# umodular_midi4_rev01.net
KiCad netlist of a schematic drawn in EAGLE
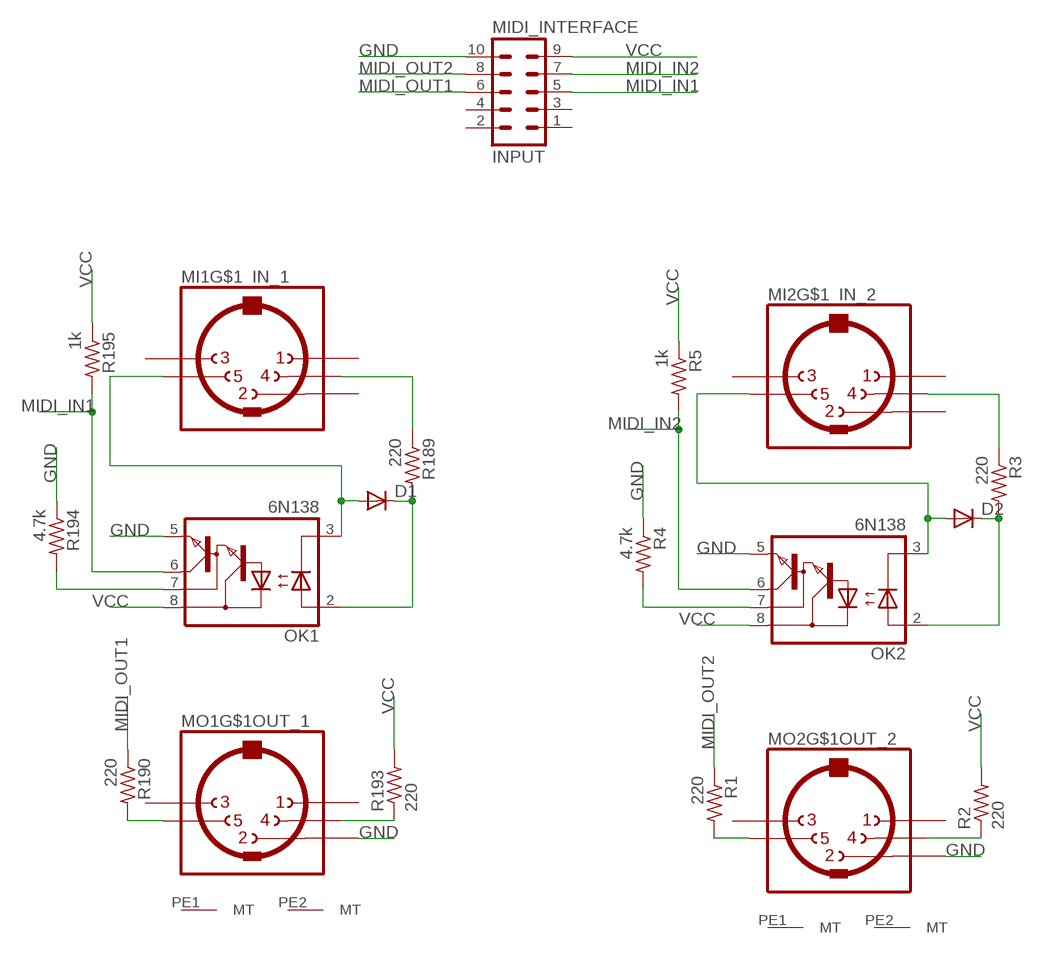
[diagram p0: schematic, sheet 1]

(export (version "E")
  (design (tool "Eeschema 10.0.6"))
  (components
    (comp (ref "D1")
      (value "1N4148DO35-7")
      (footprint "eagle-import:DO35-7")
      (libsource (lib "eagle-import") (part "1N4148DO35-7"))
    )
    (comp (ref "D2")
      (value "1N4148DO35-7")
      (footprint "eagle-import:DO35-7")
      (libsource (lib "eagle-import") (part "1N4148DO35-7"))
    )
    (comp (ref "MI1")
      (value "IN_1")
      (footprint "eagle-import:CP-2350")
      (libsource (lib "eagle-import") (part "MIDIJACK"))
    )
    (comp (ref "MI2")
      (value "IN_2")
      (footprint "eagle-import:CP-2350")
      (libsource (lib "eagle-import") (part "MIDIJACK"))
    )
    (comp (ref "MIDI_INTERFACE")
      (value "INPUT")
      (footprint "eagle-import:MA05-2")
      (libsource (lib "eagle-import") (part "MA05-2"))
    )
    (comp (ref "MO1")
      (value "OUT_1")
      (footprint "eagle-import:CP-2350")
      (libsource (lib "eagle-import") (part "MIDIJACK"))
    )
    (comp (ref "MO2")
      (value "OUT_2")
      (footprint "eagle-import:CP-2350")
      (libsource (lib "eagle-import") (part "MIDIJACK"))
    )
    (comp (ref "OK1")
      (value "6N138")
      (footprint "eagle-import:DIL08")
      (fields (field (name "MF") "VISHAY/TELEFUNKEN"))
      (libsource (lib "eagle-import") (part "6N138"))
    )
    (comp (ref "OK2")
      (value "6N138")
      (footprint "eagle-import:DIL08")
      (fields (field (name "MF") "VISHAY/TELEFUNKEN"))
      (libsource (lib "eagle-import") (part "6N138"))
    )
    (comp (ref "R1")
      (value "220")
      (footprint "eagle-import:0204_7@1")
      (libsource (lib "eagle-import") (part "R-US_0204/7"))
    )
    (comp (ref "R2")
      (value "220")
      (footprint "eagle-import:0204_7@1")
      (libsource (lib "eagle-import") (part "R-US_0204/7"))
    )
    (comp (ref "R3")
      (value "220")
      (footprint "eagle-import:0204_7@1")
      (libsource (lib "eagle-import") (part "R-US_0204/7"))
    )
    (comp (ref "R4")
      (value "4.7k")
      (footprint "eagle-import:0204_7@1")
      (libsource (lib "eagle-import") (part "R-US_0204/7"))
    )
    (comp (ref "R5")
      (value "1k")
      (footprint "eagle-import:0204_7@1")
      (libsource (lib "eagle-import") (part "R-US_0204/7"))
    )
    (comp (ref "R189")
      (value "220")
      (footprint "eagle-import:0204_7@1")
      (libsource (lib "eagle-import") (part "R-US_0204/7"))
    )
    (comp (ref "R190")
      (value "220")
      (footprint "eagle-import:0204_7@1")
      (libsource (lib "eagle-import") (part "R-US_0204/7"))
    )
    (comp (ref "R193")
      (value "220")
      (footprint "eagle-import:0204_7@1")
      (libsource (lib "eagle-import") (part "R-US_0204/7"))
    )
    (comp (ref "R194")
      (value "4.7k")
      (footprint "eagle-import:0204_7@1")
      (libsource (lib "eagle-import") (part "R-US_0204/7"))
    )
    (comp (ref "R195")
      (value "1k")
      (footprint "eagle-import:0204_7@1")
      (libsource (lib "eagle-import") (part "R-US_0204/7"))
    )
  )
  (nets
    (net (code "1") (name "/GND") (class "Default")
      (node (ref "MIDI_INTERFACE") (pin "10") (pinfunction "10_10") (pintype "passive"))
      (node (ref "MO1") (pin "2") (pinfunction "2_2") (pintype "passive"))
      (node (ref "MO2") (pin "2") (pinfunction "2_2") (pintype "passive"))
      (node (ref "OK1") (pin "5") (pinfunction "GND_5") (pintype "passive"))
      (node (ref "OK2") (pin "5") (pinfunction "GND_5") (pintype "passive"))
      (node (ref "R194") (pin "1") (pinfunction "1_1") (pintype "passive"))
      (node (ref "R4") (pin "1") (pinfunction "1_1") (pintype "passive"))
    )
    (net (code "2") (name "/MIDI_IN1") (class "Default")
      (node (ref "MIDI_INTERFACE") (pin "5") (pinfunction "5_5") (pintype "passive"))
      (node (ref "OK1") (pin "6") (pinfunction "VO_6") (pintype "passive"))
      (node (ref "R195") (pin "2") (pinfunction "2_2") (pintype "passive"))
    )
    (net (code "3") (name "/MIDI_IN2") (class "Default")
      (node (ref "MIDI_INTERFACE") (pin "7") (pinfunction "7_7") (pintype "passive"))
      (node (ref "OK2") (pin "6") (pinfunction "VO_6") (pintype "passive"))
      (node (ref "R5") (pin "2") (pinfunction "2_2") (pintype "passive"))
    )
    (net (code "4") (name "/MIDI_OUT1") (class "Default")
      (node (ref "MIDI_INTERFACE") (pin "6") (pinfunction "6_6") (pintype "passive"))
      (node (ref "R190") (pin "1") (pinfunction "1_1") (pintype "passive"))
    )
    (net (code "5") (name "/MIDI_OUT2") (class "Default")
      (node (ref "MIDI_INTERFACE") (pin "8") (pinfunction "8_8") (pintype "passive"))
      (node (ref "R1") (pin "1") (pinfunction "1_1") (pintype "passive"))
    )
    (net (code "6") (name "/VCC") (class "Default")
      (node (ref "MIDI_INTERFACE") (pin "9") (pinfunction "9_9") (pintype "passive"))
      (node (ref "OK1") (pin "8") (pinfunction "VCC_8") (pintype "passive"))
      (node (ref "OK2") (pin "8") (pinfunction "VCC_8") (pintype "passive"))
      (node (ref "R193") (pin "2") (pinfunction "2_2") (pintype "passive"))
      (node (ref "R195") (pin "1") (pinfunction "1_1") (pintype "passive"))
      (node (ref "R2") (pin "2") (pinfunction "2_2") (pintype "passive"))
      (node (ref "R5") (pin "1") (pinfunction "1_1") (pintype "passive"))
    )
    (net (code "7") (name "Net-(MI1-Pad4)") (class "Default")
      (node (ref "MI1") (pin "4") (pinfunction "4_4") (pintype "passive"))
      (node (ref "R189") (pin "1") (pinfunction "1_1") (pintype "passive"))
    )
    (net (code "8") (name "Net-(MI2-Pad4)") (class "Default")
      (node (ref "MI2") (pin "4") (pinfunction "4_4") (pintype "passive"))
      (node (ref "R3") (pin "1") (pinfunction "1_1") (pintype "passive"))
    )
    (net (code "9") (name "Net-(MO1-Pad4)") (class "Default")
      (node (ref "MO1") (pin "4") (pinfunction "4_4") (pintype "passive"))
      (node (ref "R193") (pin "1") (pinfunction "1_1") (pintype "passive"))
    )
    (net (code "10") (name "Net-(MO1-Pad5)") (class "Default")
      (node (ref "MO1") (pin "5") (pinfunction "5_5") (pintype "passive"))
      (node (ref "R190") (pin "2") (pinfunction "2_2") (pintype "passive"))
    )
    (net (code "11") (name "Net-(MO2-Pad4)") (class "Default")
      (node (ref "MO2") (pin "4") (pinfunction "4_4") (pintype "passive"))
      (node (ref "R2") (pin "1") (pinfunction "1_1") (pintype "passive"))
    )
    (net (code "12") (name "Net-(MO2-Pad5)") (class "Default")
      (node (ref "MO2") (pin "5") (pinfunction "5_5") (pintype "passive"))
      (node (ref "R1") (pin "2") (pinfunction "2_2") (pintype "passive"))
    )
    (net (code "13") (name "Net-(OK1-A)") (class "Default")
      (node (ref "D1") (pin "C") (pinfunction "C_C") (pintype "passive"))
      (node (ref "OK1") (pin "2") (pinfunction "A_2") (pintype "passive"))
      (node (ref "R189") (pin "2") (pinfunction "2_2") (pintype "passive"))
    )
    (net (code "14") (name "Net-(OK1-C)") (class "Default")
      (node (ref "D1") (pin "A") (pinfunction "A_A") (pintype "passive"))
      (node (ref "MI1") (pin "5") (pinfunction "5_5") (pintype "passive"))
      (node (ref "OK1") (pin "3") (pinfunction "C_3") (pintype "passive"))
    )
    (net (code "15") (name "Net-(OK1-VB)") (class "Default")
      (node (ref "OK1") (pin "7") (pinfunction "VB_7") (pintype "passive"))
      (node (ref "R194") (pin "2") (pinfunction "2_2") (pintype "passive"))
    )
    (net (code "16") (name "Net-(OK2-A)") (class "Default")
      (node (ref "D2") (pin "C") (pinfunction "C_C") (pintype "passive"))
      (node (ref "OK2") (pin "2") (pinfunction "A_2") (pintype "passive"))
      (node (ref "R3") (pin "2") (pinfunction "2_2") (pintype "passive"))
    )
    (net (code "17") (name "Net-(OK2-C)") (class "Default")
      (node (ref "D2") (pin "A") (pinfunction "A_A") (pintype "passive"))
      (node (ref "MI2") (pin "5") (pinfunction "5_5") (pintype "passive"))
      (node (ref "OK2") (pin "3") (pinfunction "C_3") (pintype "passive"))
    )
    (net (code "18") (name "Net-(OK2-VB)") (class "Default")
      (node (ref "OK2") (pin "7") (pinfunction "VB_7") (pintype "passive"))
      (node (ref "R4") (pin "2") (pinfunction "2_2") (pintype "passive"))
    )
    (net (code "19") (name "unconnected-(MI1-Pad1)") (class "Default")
      (node (ref "MI1") (pin "1") (pinfunction "1_1") (pintype "passive"))
    )
    (net (code "20") (name "unconnected-(MI1-Pad2)") (class "Default")
      (node (ref "MI1") (pin "2") (pinfunction "2_2") (pintype "passive"))
    )
    (net (code "21") (name "unconnected-(MI1-Pad3)") (class "Default")
      (node (ref "MI1") (pin "3") (pinfunction "3_3") (pintype "passive"))
    )
    (net (code "22") (name "unconnected-(MI2-Pad1)") (class "Default")
      (node (ref "MI2") (pin "1") (pinfunction "1_1") (pintype "passive"))
    )
    (net (code "23") (name "unconnected-(MI2-Pad2)") (class "Default")
      (node (ref "MI2") (pin "2") (pinfunction "2_2") (pintype "passive"))
    )
    (net (code "24") (name "unconnected-(MI2-Pad3)") (class "Default")
      (node (ref "MI2") (pin "3") (pinfunction "3_3") (pintype "passive"))
    )
    (net (code "25") (name "unconnected-(MIDI_INTERFACE-Pad1)") (class "Default")
      (node (ref "MIDI_INTERFACE") (pin "1") (pinfunction "1_1") (pintype "passive"))
    )
    (net (code "26") (name "unconnected-(MIDI_INTERFACE-Pad2)") (class "Default")
      (node (ref "MIDI_INTERFACE") (pin "2") (pinfunction "2_2") (pintype "passive"))
    )
    (net (code "27") (name "unconnected-(MIDI_INTERFACE-Pad3)") (class "Default")
      (node (ref "MIDI_INTERFACE") (pin "3") (pinfunction "3_3") (pintype "passive"))
    )
    (net (code "28") (name "unconnected-(MIDI_INTERFACE-Pad4)") (class "Default")
      (node (ref "MIDI_INTERFACE") (pin "4") (pinfunction "4_4") (pintype "passive"))
    )
    (net (code "29") (name "unconnected-(MO1-Pad1)") (class "Default")
      (node (ref "MO1") (pin "1") (pinfunction "1_1") (pintype "passive"))
    )
    (net (code "30") (name "unconnected-(MO1-Pad3)") (class "Default")
      (node (ref "MO1") (pin "3") (pinfunction "3_3") (pintype "passive"))
    )
    (net (code "31") (name "unconnected-(MO1D-MT-PadPE1)") (class "Default")
      (node (ref "MO1") (pin "PE1") (pinfunction "MT_PE1") (pintype "passive"))
    )
    (net (code "32") (name "unconnected-(MO1E-MT-PadPE2)") (class "Default")
      (node (ref "MO1") (pin "PE2") (pinfunction "MT_PE2") (pintype "passive"))
    )
    (net (code "33") (name "unconnected-(MO2-Pad1)") (class "Default")
      (node (ref "MO2") (pin "1") (pinfunction "1_1") (pintype "passive"))
    )
    (net (code "34") (name "unconnected-(MO2-Pad3)") (class "Default")
      (node (ref "MO2") (pin "3") (pinfunction "3_3") (pintype "passive"))
    )
    (net (code "35") (name "unconnected-(MO2D-MT-PadPE1)") (class "Default")
      (node (ref "MO2") (pin "PE1") (pinfunction "MT_PE1") (pintype "passive"))
    )
    (net (code "36") (name "unconnected-(MO2E-MT-PadPE2)") (class "Default")
      (node (ref "MO2") (pin "PE2") (pinfunction "MT_PE2") (pintype "passive"))
    )
  )
)
